# breakout_motor_driver.net
KiCad netlist of a schematic drawn in EAGLE
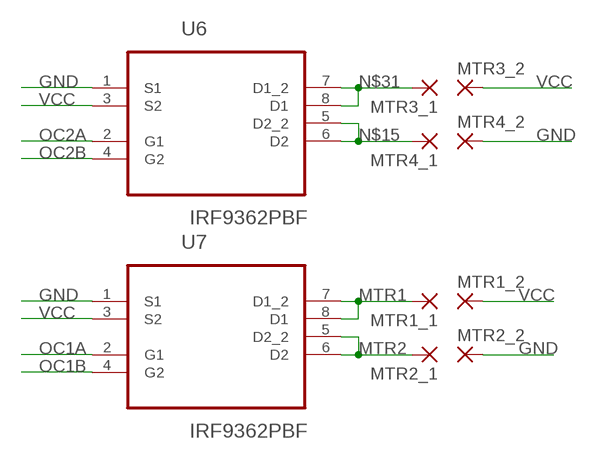
[diagram p0: schematic, sheet 1]

(export (version "E")
  (design (tool "Eeschema 10.0.6"))
  (components
    (comp (ref "MTR1_1")
      (value "1,6/0,8")
      (footprint "eagle-import:1,6_0,8")
      (libsource (lib "eagle-import") (part "1,6/0,8"))
    )
    (comp (ref "MTR1_2")
      (value "1,6/0,8")
      (footprint "eagle-import:1,6_0,8")
      (libsource (lib "eagle-import") (part "1,6/0,8"))
    )
    (comp (ref "MTR2_1")
      (value "1,6/0,8")
      (footprint "eagle-import:1,6_0,8")
      (libsource (lib "eagle-import") (part "1,6/0,8"))
    )
    (comp (ref "MTR2_2")
      (value "1,6/0,8")
      (footprint "eagle-import:1,6_0,8")
      (libsource (lib "eagle-import") (part "1,6/0,8"))
    )
    (comp (ref "MTR3_1")
      (value "1,6/0,8")
      (footprint "eagle-import:1,6_0,8")
      (libsource (lib "eagle-import") (part "1,6/0,8"))
    )
    (comp (ref "MTR3_2")
      (value "1,6/0,8")
      (footprint "eagle-import:1,6_0,8")
      (libsource (lib "eagle-import") (part "1,6/0,8"))
    )
    (comp (ref "MTR4_1")
      (value "1,6/0,8")
      (footprint "eagle-import:1,6_0,8")
      (libsource (lib "eagle-import") (part "1,6/0,8"))
    )
    (comp (ref "MTR4_2")
      (value "1,6/0,8")
      (footprint "eagle-import:1,6_0,8")
      (libsource (lib "eagle-import") (part "1,6/0,8"))
    )
    (comp (ref "U6")
      (value "IRF9362PBF")
      (footprint "eagle-import:SOIC127P600X175-8N")
      (libsource (lib "eagle-import") (part "IRF9362PBF"))
    )
    (comp (ref "U7")
      (value "IRF9362PBF")
      (footprint "eagle-import:SOIC127P600X175-8N")
      (libsource (lib "eagle-import") (part "IRF9362PBF"))
    )
  )
  (nets
    (net (code "1") (name "/GND") (class "Default")
      (node (ref "MTR2_2") (pin "1") (pinfunction "P_1") (pintype "passive"))
      (node (ref "MTR4_2") (pin "1") (pinfunction "P_1") (pintype "passive"))
      (node (ref "U6") (pin "1") (pinfunction "S1_1") (pintype "passive"))
      (node (ref "U7") (pin "1") (pinfunction "S1_1") (pintype "passive"))
    )
    (net (code "2") (name "/MTR1") (class "Default")
      (node (ref "MTR1_1") (pin "1") (pinfunction "P_1") (pintype "passive"))
      (node (ref "U7") (pin "7") (pinfunction "D1_2_7") (pintype "passive"))
      (node (ref "U7") (pin "8") (pinfunction "D1_8") (pintype "passive"))
    )
    (net (code "3") (name "/MTR2") (class "Default")
      (node (ref "MTR2_1") (pin "1") (pinfunction "P_1") (pintype "passive"))
      (node (ref "U7") (pin "5") (pinfunction "D2_2_5") (pintype "passive"))
      (node (ref "U7") (pin "6") (pinfunction "D2_6") (pintype "passive"))
    )
    (net (code "4") (name "/N$15") (class "Default")
      (node (ref "MTR4_1") (pin "1") (pinfunction "P_1") (pintype "passive"))
      (node (ref "U6") (pin "5") (pinfunction "D2_2_5") (pintype "passive"))
      (node (ref "U6") (pin "6") (pinfunction "D2_6") (pintype "passive"))
    )
    (net (code "5") (name "/N$31") (class "Default")
      (node (ref "MTR3_1") (pin "1") (pinfunction "P_1") (pintype "passive"))
      (node (ref "U6") (pin "7") (pinfunction "D1_2_7") (pintype "passive"))
      (node (ref "U6") (pin "8") (pinfunction "D1_8") (pintype "passive"))
    )
    (net (code "6") (name "/OC1A") (class "Default")
      (node (ref "U7") (pin "2") (pinfunction "G1_2") (pintype "passive"))
    )
    (net (code "7") (name "/OC1B") (class "Default")
      (node (ref "U7") (pin "4") (pinfunction "G2_4") (pintype "passive"))
    )
    (net (code "8") (name "/OC2A") (class "Default")
      (node (ref "U6") (pin "2") (pinfunction "G1_2") (pintype "passive"))
    )
    (net (code "9") (name "/OC2B") (class "Default")
      (node (ref "U6") (pin "4") (pinfunction "G2_4") (pintype "passive"))
    )
    (net (code "10") (name "/VCC") (class "Default")
      (node (ref "MTR1_2") (pin "1") (pinfunction "P_1") (pintype "passive"))
      (node (ref "MTR3_2") (pin "1") (pinfunction "P_1") (pintype "passive"))
      (node (ref "U6") (pin "3") (pinfunction "S2_3") (pintype "passive"))
      (node (ref "U7") (pin "3") (pinfunction "S2_3") (pintype "passive"))
    )
  )
)
